# DriverPCB.net
KiCad netlist of a schematic drawn in Altium Designer
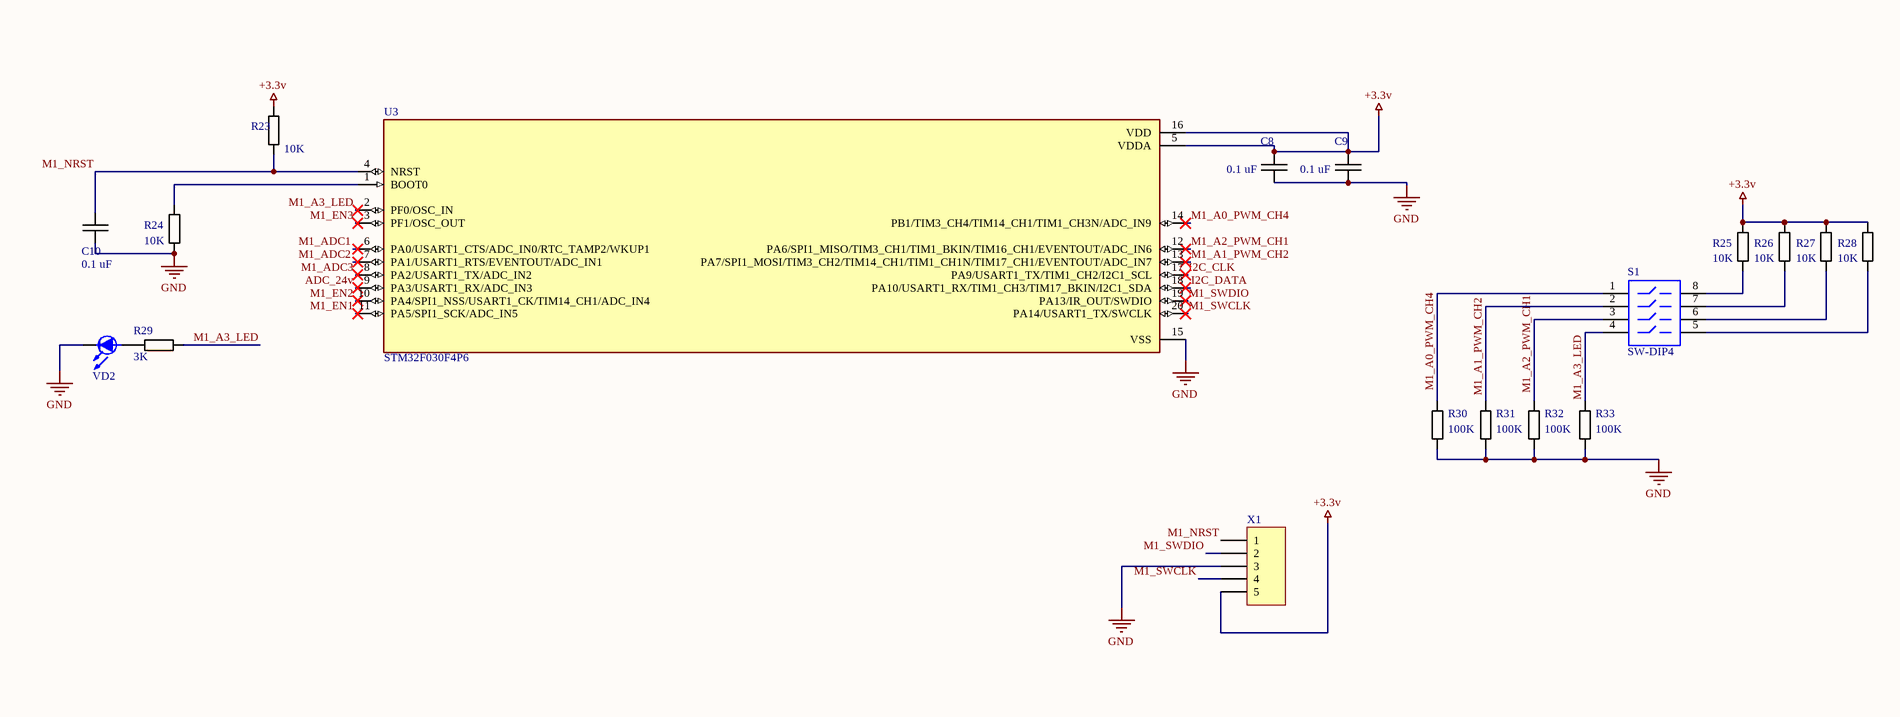
[diagram p0: DriverPCB.SchDoc, top left]
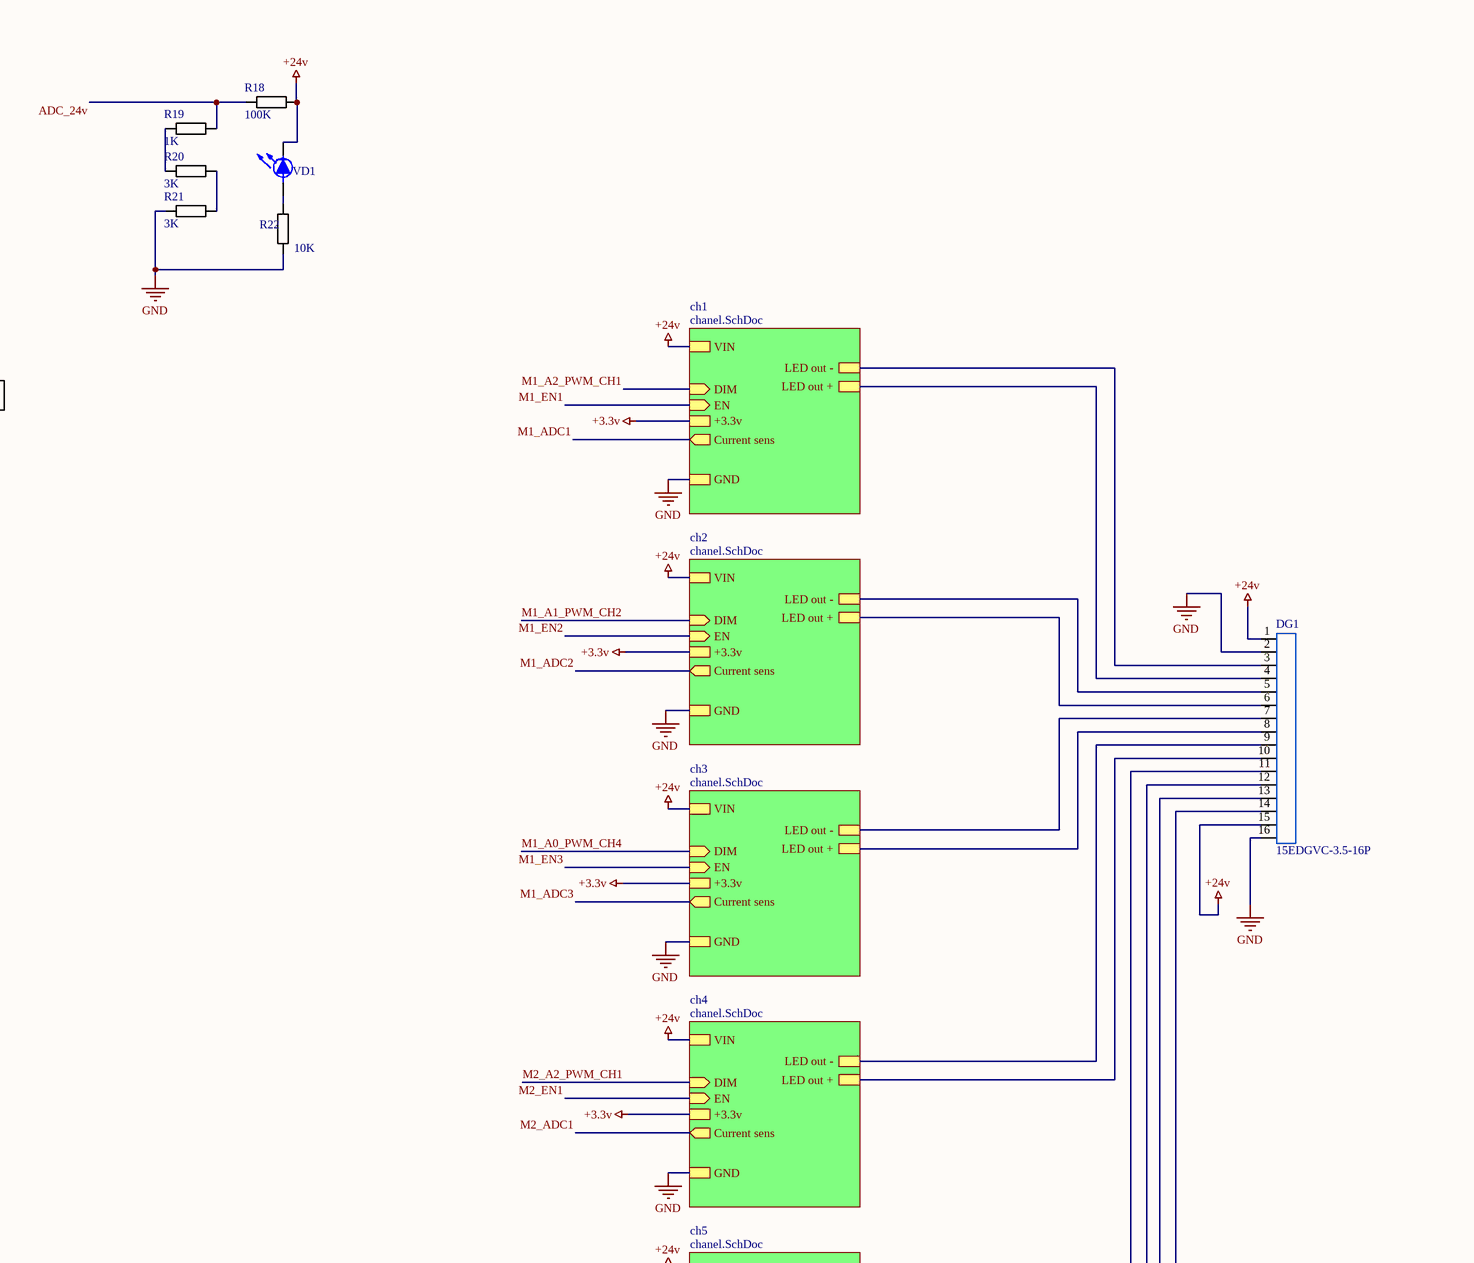
[diagram p1: DriverPCB.SchDoc, top right]
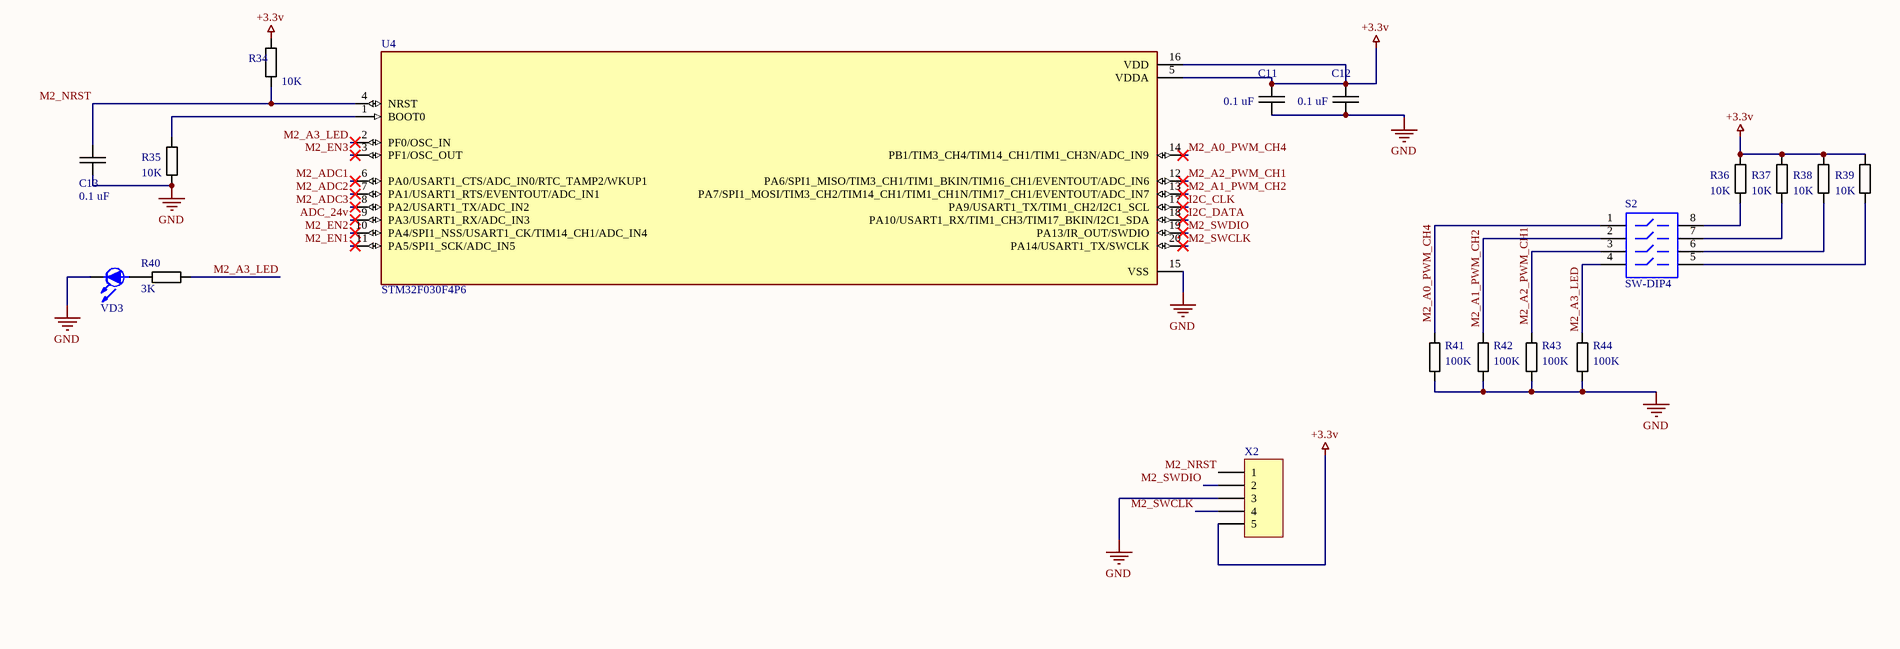
[diagram p2: DriverPCB.SchDoc, bottom left]
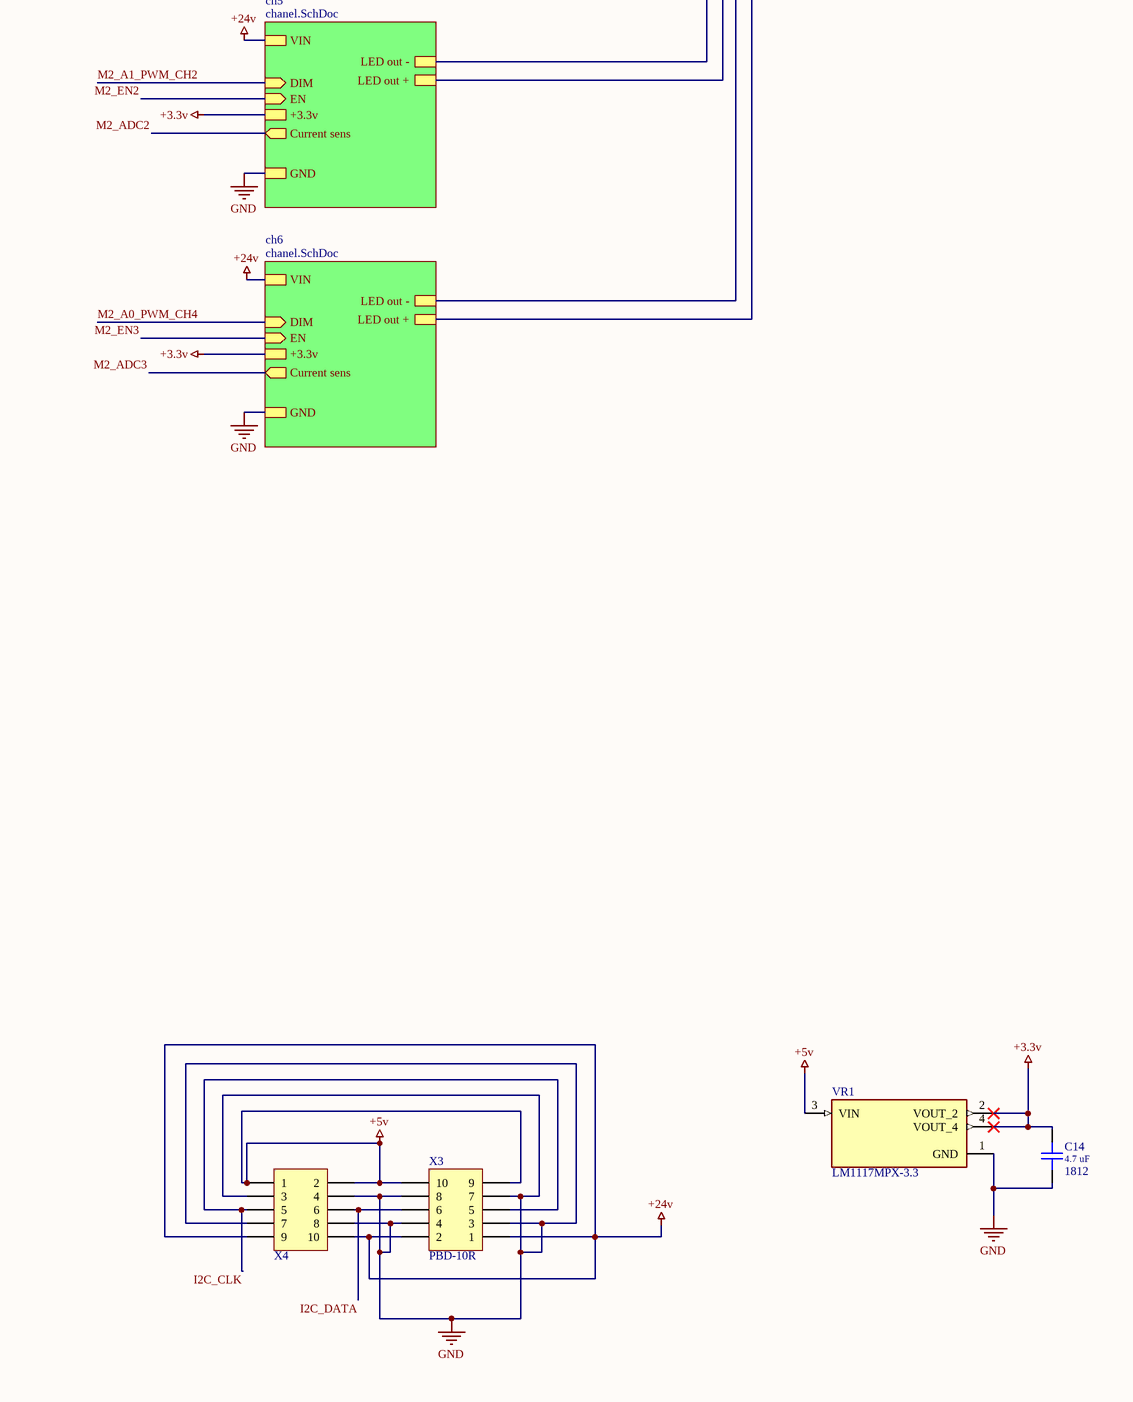
[diagram p3: DriverPCB.SchDoc, bottom right]

(export (version "E")
  (design (tool "Eeschema 10.0.6"))
  (components
    (comp (ref "C8")
      (value "0.1 uF")
      (footprint "CAPACITOR 0603")
      (libsource (lib "Maks_lib") (part "Capasitor"))
    )
    (comp (ref "C9")
      (value "0.1 uF")
      (footprint "CAPACITOR 0603")
      (libsource (lib "Maks_lib") (part "Capasitor"))
    )
    (comp (ref "C10")
      (value "0.1 uF")
      (footprint "CAPACITOR 0603")
      (libsource (lib "Maks_lib") (part "Capasitor"))
    )
    (comp (ref "C11")
      (value "0.1 uF")
      (footprint "CAPACITOR 0603")
      (libsource (lib "Maks_lib") (part "Capasitor"))
    )
    (comp (ref "C12")
      (value "0.1 uF")
      (footprint "CAPACITOR 0603")
      (libsource (lib "Maks_lib") (part "Capasitor"))
    )
    (comp (ref "C13")
      (value "0.1 uF")
      (footprint "CAPACITOR 0603")
      (libsource (lib "Maks_lib") (part "Capasitor"))
    )
    (comp (ref "C14")
      (value "4.7 uF")
      (footprint "CAPCHIP1812")
      (description "Ceramic Capacitor")
      (fields (field (name "PACKAGE") "1812") (field (name "Comment") "Cap C"))
      (libsource (lib "RCL") (part "Cap C"))
    )
    (comp (ref "DG1")
      (value "15EDGVC-3.5-16P")
      (footprint "15EDGVC-3.5-16P")
      (libsource (lib "Degson") (part "15EDGVC-3.5-16P"))
    )
    (comp (ref "R18")
      (value "100K")
      (footprint "Resistor 0402")
      (libsource (lib "Maks_lib") (part "Resistor"))
    )
    (comp (ref "R19") (value "1K") (footprint "Resistor 0402") (libsource (lib "Maks_lib") (part "Resistor")))
    (comp (ref "R20") (value "3K") (footprint "Resistor 0402") (libsource (lib "Maks_lib") (part "Resistor")))
    (comp (ref "R21") (value "3K") (footprint "Resistor 0402") (libsource (lib "Maks_lib") (part "Resistor")))
    (comp (ref "R22")
      (value "10K")
      (footprint "Resistor 0402")
      (libsource (lib "Maks_lib") (part "Resistor"))
    )
    (comp (ref "R23")
      (value "10K")
      (footprint "Resistor 0402")
      (libsource (lib "Maks_lib") (part "Resistor"))
    )
    (comp (ref "R24")
      (value "10K")
      (footprint "Resistor 0402")
      (libsource (lib "Maks_lib") (part "Resistor"))
    )
    (comp (ref "R25")
      (value "10K")
      (footprint "Resistor 0402")
      (libsource (lib "Maks_lib") (part "Resistor"))
    )
    (comp (ref "R26")
      (value "10K")
      (footprint "Resistor 0402")
      (libsource (lib "Maks_lib") (part "Resistor"))
    )
    (comp (ref "R27")
      (value "10K")
      (footprint "Resistor 0402")
      (libsource (lib "Maks_lib") (part "Resistor"))
    )
    (comp (ref "R28")
      (value "10K")
      (footprint "Resistor 0402")
      (libsource (lib "Maks_lib") (part "Resistor"))
    )
    (comp (ref "R29") (value "3K") (footprint "Resistor 0402") (libsource (lib "Maks_lib") (part "Resistor")))
    (comp (ref "R30")
      (value "100K")
      (footprint "Resistor 0402")
      (libsource (lib "Maks_lib") (part "Resistor"))
    )
    (comp (ref "R31")
      (value "100K")
      (footprint "Resistor 0402")
      (libsource (lib "Maks_lib") (part "Resistor"))
    )
    (comp (ref "R32")
      (value "100K")
      (footprint "Resistor 0402")
      (libsource (lib "Maks_lib") (part "Resistor"))
    )
    (comp (ref "R33")
      (value "100K")
      (footprint "Resistor 0402")
      (libsource (lib "Maks_lib") (part "Resistor"))
    )
    (comp (ref "R34")
      (value "10K")
      (footprint "Resistor 0402")
      (libsource (lib "Maks_lib") (part "Resistor"))
    )
    (comp (ref "R35")
      (value "10K")
      (footprint "Resistor 0402")
      (libsource (lib "Maks_lib") (part "Resistor"))
    )
    (comp (ref "R36")
      (value "10K")
      (footprint "Resistor 0402")
      (libsource (lib "Maks_lib") (part "Resistor"))
    )
    (comp (ref "R37")
      (value "10K")
      (footprint "Resistor 0402")
      (libsource (lib "Maks_lib") (part "Resistor"))
    )
    (comp (ref "R38")
      (value "10K")
      (footprint "Resistor 0402")
      (libsource (lib "Maks_lib") (part "Resistor"))
    )
    (comp (ref "R39")
      (value "10K")
      (footprint "Resistor 0402")
      (libsource (lib "Maks_lib") (part "Resistor"))
    )
    (comp (ref "R40") (value "3K") (footprint "Resistor 0402") (libsource (lib "Maks_lib") (part "Resistor")))
    (comp (ref "R41")
      (value "100K")
      (footprint "Resistor 0402")
      (libsource (lib "Maks_lib") (part "Resistor"))
    )
    (comp (ref "R42")
      (value "100K")
      (footprint "Resistor 0402")
      (libsource (lib "Maks_lib") (part "Resistor"))
    )
    (comp (ref "R43")
      (value "100K")
      (footprint "Resistor 0402")
      (libsource (lib "Maks_lib") (part "Resistor"))
    )
    (comp (ref "R44")
      (value "100K")
      (footprint "Resistor 0402")
      (libsource (lib "Maks_lib") (part "Resistor"))
    )
    (comp (ref "S1")
      (value "SW-DIP4")
      (footprint "DIP-8")
      (description "DIP Switch")
      (fields (field (name "PUBLISHER") "Altium Limited"))
      (libsource (lib "Miscellaneous Devices") (part "SW-DIP4"))
    )
    (comp (ref "S2")
      (value "SW-DIP4")
      (footprint "DIP-8")
      (description "DIP Switch")
      (fields (field (name "PUBLISHER") "Altium Limited"))
      (libsource (lib "Miscellaneous Devices") (part "SW-DIP4"))
    )
    (comp (ref "U3")
      (value "STM32F030F4P6")
      (footprint "SOP65P640X120-20N")
      (description "MCU 32-bit STM32F ARM Cortex M0 RISC 16KB Flash 2.5V/3.3V 20-Pin TSSOP Tray")
      (libsource (lib "STM32F030F4P6") (part "STM32F030F4P6"))
    )
    (comp (ref "U4")
      (value "STM32F030F4P6")
      (footprint "SOP65P640X120-20N")
      (description "MCU 32-bit STM32F ARM Cortex M0 RISC 16KB Flash 2.5V/3.3V 20-Pin TSSOP Tray")
      (libsource (lib "STM32F030F4P6") (part "STM32F030F4P6"))
    )
    (comp (ref "VD1") (value "one color") (footprint "0805-") (libsource (lib "DT") (part "LED SMD")))
    (comp (ref "VD2") (value "~") (footprint "0805-") (libsource (lib "DT") (part "LED SMD")))
    (comp (ref "VD3") (value "~") (footprint "0805-") (libsource (lib "DT") (part "LED SMD")))
    (comp (ref "VR1")
      (value "LM1117MPX-3.3")
      (footprint "VREG_LM1117MPX-3.3")
      (description "800-mA 15-V linear voltage regulator")
      (fields (field (name "MF") "Texas Instruments"))
      (libsource (lib "LM1117MPX-3.3") (part "LM1117MPX-3.3"))
    )
    (comp (ref "X1")
      (value "~")
      (footprint "PLS-5-3D")
      (description "Header, 5-Pin")
      (fields (field (name "PARTNUMBER") "PLS-5"))
      (libsource (lib "AX_Altium_v2.3") (part "PLS-5"))
    )
    (comp (ref "X2")
      (value "~")
      (footprint "PLS-5-3D")
      (description "Header, 5-Pin")
      (fields (field (name "PARTNUMBER") "PLS-5"))
      (libsource (lib "AX_Altium_v2.3") (part "PLS-5"))
    )
    (comp (ref "X3")
      (value "PBD-10R")
      (footprint "PBD-10RR")
      (description "Header, 5-Pin, Dual row")
      (libsource (lib "AX_Altium_v2.3") (part "PBD-10R"))
    )
    (comp (ref "X4")
      (value "PLD-10R")
      (footprint "PLD-10RR1")
      (description "Header, 5-Pin, Dual row")
      (libsource (lib "AX_Altium_v2.3") (part "PLD-10R"))
    )
  )
  (nets
    (net (code "1") (name "+3.3v") (class "Default")
      (node (ref "C11") (pin "1") (pinfunction "1_1") (pintype "passive"))
      (node (ref "C12") (pin "1") (pinfunction "1_1") (pintype "passive"))
      (node (ref "C14") (pin "2") (pinfunction "2_2") (pintype "passive"))
      (node (ref "C8") (pin "1") (pinfunction "1_1") (pintype "passive"))
      (node (ref "C9") (pin "1") (pinfunction "1_1") (pintype "passive"))
      (node (ref "R23") (pin "2") (pinfunction "2_2") (pintype "passive"))
      (node (ref "R25") (pin "1") (pinfunction "1_1") (pintype "passive"))
      (node (ref "R26") (pin "1") (pinfunction "1_1") (pintype "passive"))
      (node (ref "R27") (pin "1") (pinfunction "1_1") (pintype "passive"))
      (node (ref "R28") (pin "1") (pinfunction "1_1") (pintype "passive"))
      (node (ref "R34") (pin "2") (pinfunction "2_2") (pintype "passive"))
      (node (ref "R36") (pin "1") (pinfunction "1_1") (pintype "passive"))
      (node (ref "R37") (pin "1") (pinfunction "1_1") (pintype "passive"))
      (node (ref "R38") (pin "1") (pinfunction "1_1") (pintype "passive"))
      (node (ref "R39") (pin "1") (pinfunction "1_1") (pintype "passive"))
      (node (ref "U3") (pin "16") (pinfunction "VDD_16") (pintype "power_in"))
      (node (ref "U3") (pin "5") (pinfunction "VDDA_5") (pintype "power_in"))
      (node (ref "U4") (pin "16") (pinfunction "VDD_16") (pintype "power_in"))
      (node (ref "U4") (pin "5") (pinfunction "VDDA_5") (pintype "power_in"))
      (node (ref "VR1") (pin "2") (pinfunction "VOUT_2_2") (pintype "output"))
      (node (ref "VR1") (pin "4") (pinfunction "VOUT_4_4") (pintype "output"))
      (node (ref "X1") (pin "5") (pinfunction "5_5") (pintype "passive"))
      (node (ref "X2") (pin "5") (pinfunction "5_5") (pintype "passive"))
    )
    (net (code "2") (name "+5v") (class "Default")
      (node (ref "VR1") (pin "3") (pinfunction "VIN_3") (pintype "input"))
      (node (ref "X3") (pin "10") (pinfunction "10_10") (pintype "passive"))
      (node (ref "X3") (pin "9") (pinfunction "9_9") (pintype "passive"))
      (node (ref "X4") (pin "1") (pinfunction "1_1") (pintype "passive"))
      (node (ref "X4") (pin "2") (pinfunction "2_2") (pintype "passive"))
    )
    (net (code "3") (name "+24v") (class "Default")
      (node (ref "DG1") (pin "1") (pintype "passive"))
      (node (ref "DG1") (pin "15") (pintype "passive"))
      (node (ref "R18") (pin "1") (pinfunction "1_1") (pintype "passive"))
      (node (ref "VD1") (pin "K") (pinfunction "k_K") (pintype "passive"))
      (node (ref "X3") (pin "1") (pinfunction "1_1") (pintype "passive"))
      (node (ref "X3") (pin "2") (pinfunction "2_2") (pintype "passive"))
      (node (ref "X4") (pin "10") (pinfunction "10_10") (pintype "passive"))
      (node (ref "X4") (pin "9") (pinfunction "9_9") (pintype "passive"))
    )
    (net (code "4") (name "/ADC_24v") (class "Default")
      (node (ref "R18") (pin "2") (pinfunction "2_2") (pintype "passive"))
      (node (ref "R19") (pin "2") (pinfunction "2_2") (pintype "passive"))
      (node (ref "U3") (pin "9") (pinfunction "PA3/USART1_RX/ADC_IN3_9") (pintype "bidirectional"))
      (node (ref "U4") (pin "9") (pinfunction "PA3/USART1_RX/ADC_IN3_9") (pintype "bidirectional"))
    )
    (net (code "7") (name "/I2C_CLK") (class "Default")
      (node (ref "U3") (pin "17") (pinfunction "PA9/USART1_TX/TIM1_CH2/I2C1_SCL_17") (pintype "bidirectional"))
      (node (ref "U4") (pin "17") (pinfunction "PA9/USART1_TX/TIM1_CH2/I2C1_SCL_17") (pintype "bidirectional"))
      (node (ref "X3") (pin "5") (pinfunction "5_5") (pintype "passive"))
      (node (ref "X4") (pin "5") (pinfunction "5_5") (pintype "passive"))
    )
    (net (code "8") (name "/I2C_DATA") (class "Default")
      (node (ref "U3") (pin "18") (pinfunction "PA10/USART1_RX/TIM1_CH3/TIM17_BKIN/I2C1_SDA_18") (pintype "bidirectional"))
      (node (ref "U4") (pin "18") (pinfunction "PA10/USART1_RX/TIM1_CH3/TIM17_BKIN/I2C1_SDA_18") (pintype "bidirectional"))
      (node (ref "X3") (pin "6") (pinfunction "6_6") (pintype "passive"))
      (node (ref "X4") (pin "6") (pinfunction "6_6") (pintype "passive"))
    )
    (net (code "9") (name "/LED out +") (class "Default") (node (ref "DG1") (pin "12") (pintype "passive")))
    (net (code "10") (name "/LED out +_1") (class "Default")
      (node (ref "DG1") (pin "14") (pintype "passive"))
    )
    (net (code "11") (name "/LED out +_2") (class "Default") (node (ref "DG1") (pin "8") (pintype "passive")))
    (net (code "12") (name "/LED out +_3") (class "Default") (node (ref "DG1") (pin "6") (pintype "passive")))
    (net (code "13") (name "/LED out +_4") (class "Default") (node (ref "DG1") (pin "4") (pintype "passive")))
    (net (code "14") (name "/LED out +_5") (class "Default")
      (node (ref "DG1") (pin "10") (pintype "passive"))
    )
    (net (code "15") (name "/LED out -") (class "Default") (node (ref "DG1") (pin "9") (pintype "passive")))
    (net (code "16") (name "/LED out -_1") (class "Default")
      (node (ref "DG1") (pin "13") (pintype "passive"))
    )
    (net (code "17") (name "/LED out -_2") (class "Default") (node (ref "DG1") (pin "5") (pintype "passive")))
    (net (code "18") (name "/LED out -_3") (class "Default") (node (ref "DG1") (pin "7") (pintype "passive")))
    (net (code "19") (name "/LED out -_4") (class "Default") (node (ref "DG1") (pin "3") (pintype "passive")))
    (net (code "20") (name "/LED out -_5") (class "Default")
      (node (ref "DG1") (pin "11") (pintype "passive"))
    )
    (net (code "21") (name "/M1_A0_PWM_CH4") (class "Default")
      (node (ref "R30") (pin "1") (pinfunction "1_1") (pintype "passive"))
      (node (ref "S1") (pin "1") (pinfunction "1_1") (pintype "passive"))
      (node (ref "U3") (pin "14") (pinfunction "PB1/TIM3_CH4/TIM14_CH1/TIM1_CH3N/ADC_IN9_14") (pintype "bidirectional"))
    )
    (net (code "22") (name "/M1_A1_PWM_CH2") (class "Default")
      (node (ref "R31") (pin "1") (pinfunction "1_1") (pintype "passive"))
      (node (ref "S1") (pin "2") (pinfunction "2_2") (pintype "passive"))
      (node (ref "U3") (pin "13") (pinfunction "PA7/SPI1_MOSI/TIM3_CH2/TIM14_CH1/TIM1_CH1N/TIM17_CH1/EVENTOUT/ADC_IN7_13") (pintype "bidirectional"))
    )
    (net (code "23") (name "/M1_A2_PWM_CH1") (class "Default")
      (node (ref "R32") (pin "1") (pinfunction "1_1") (pintype "passive"))
      (node (ref "S1") (pin "3") (pinfunction "3_3") (pintype "passive"))
      (node (ref "U3") (pin "12") (pinfunction "PA6/SPI1_MISO/TIM3_CH1/TIM1_BKIN/TIM16_CH1/EVENTOUT/ADC_IN6_12") (pintype "bidirectional"))
    )
    (net (code "24") (name "/M1_A3_LED") (class "Default")
      (node (ref "R29") (pin "1") (pinfunction "1_1") (pintype "passive"))
      (node (ref "R33") (pin "1") (pinfunction "1_1") (pintype "passive"))
      (node (ref "S1") (pin "4") (pinfunction "4_4") (pintype "passive"))
      (node (ref "U3") (pin "2") (pinfunction "PF0/OSC_IN_2") (pintype "bidirectional"))
    )
    (net (code "25") (name "/M1_ADC1") (class "Default")
      (node (ref "U3") (pin "6") (pinfunction "PA0/USART1_CTS/ADC_IN0/RTC_TAMP2/WKUP1_6") (pintype "bidirectional+no_connect"))
    )
    (net (code "26") (name "/M1_ADC2") (class "Default")
      (node (ref "U3") (pin "7") (pinfunction "PA1/USART1_RTS/EVENTOUT/ADC_IN1_7") (pintype "bidirectional+no_connect"))
    )
    (net (code "27") (name "/M1_ADC3") (class "Default")
      (node (ref "U3") (pin "8") (pinfunction "PA2/USART1_TX/ADC_IN2_8") (pintype "bidirectional+no_connect"))
    )
    (net (code "28") (name "/M1_EN1") (class "Default")
      (node (ref "U3") (pin "11") (pinfunction "PA5/SPI1_SCK/ADC_IN5_11") (pintype "bidirectional+no_connect"))
    )
    (net (code "29") (name "/M1_EN2") (class "Default")
      (node (ref "U3") (pin "10") (pinfunction "PA4/SPI1_NSS/USART1_CK/TIM14_CH1/ADC_IN4_10") (pintype "bidirectional+no_connect"))
    )
    (net (code "30") (name "/M1_EN3") (class "Default")
      (node (ref "U3") (pin "3") (pinfunction "PF1/OSC_OUT_3") (pintype "bidirectional+no_connect"))
    )
    (net (code "31") (name "/M1_NRST") (class "Default")
      (node (ref "C10") (pin "2") (pinfunction "2_2") (pintype "passive"))
      (node (ref "R23") (pin "1") (pinfunction "1_1") (pintype "passive"))
      (node (ref "U3") (pin "4") (pinfunction "NRST_4") (pintype "bidirectional"))
      (node (ref "X1") (pin "1") (pinfunction "1_1") (pintype "passive"))
    )
    (net (code "32") (name "/M1_SWCLK") (class "Default")
      (node (ref "U3") (pin "20") (pinfunction "PA14/USART1_TX/SWCLK_20") (pintype "bidirectional"))
      (node (ref "X1") (pin "4") (pinfunction "4_4") (pintype "passive"))
    )
    (net (code "33") (name "/M1_SWDIO") (class "Default")
      (node (ref "U3") (pin "19") (pinfunction "PA13/IR_OUT/SWDIO_19") (pintype "bidirectional"))
      (node (ref "X1") (pin "2") (pinfunction "2_2") (pintype "passive"))
    )
    (net (code "34") (name "/M2_A0_PWM_CH4") (class "Default")
      (node (ref "R41") (pin "1") (pinfunction "1_1") (pintype "passive"))
      (node (ref "S2") (pin "1") (pinfunction "1_1") (pintype "passive"))
      (node (ref "U4") (pin "14") (pinfunction "PB1/TIM3_CH4/TIM14_CH1/TIM1_CH3N/ADC_IN9_14") (pintype "bidirectional"))
    )
    (net (code "35") (name "/M2_A1_PWM_CH2") (class "Default")
      (node (ref "R42") (pin "1") (pinfunction "1_1") (pintype "passive"))
      (node (ref "S2") (pin "2") (pinfunction "2_2") (pintype "passive"))
      (node (ref "U4") (pin "13") (pinfunction "PA7/SPI1_MOSI/TIM3_CH2/TIM14_CH1/TIM1_CH1N/TIM17_CH1/EVENTOUT/ADC_IN7_13") (pintype "bidirectional"))
    )
    (net (code "36") (name "/M2_A2_PWM_CH1") (class "Default")
      (node (ref "R43") (pin "1") (pinfunction "1_1") (pintype "passive"))
      (node (ref "S2") (pin "3") (pinfunction "3_3") (pintype "passive"))
      (node (ref "U4") (pin "12") (pinfunction "PA6/SPI1_MISO/TIM3_CH1/TIM1_BKIN/TIM16_CH1/EVENTOUT/ADC_IN6_12") (pintype "bidirectional"))
    )
    (net (code "37") (name "/M2_A3_LED") (class "Default")
      (node (ref "R40") (pin "1") (pinfunction "1_1") (pintype "passive"))
      (node (ref "R44") (pin "1") (pinfunction "1_1") (pintype "passive"))
      (node (ref "S2") (pin "4") (pinfunction "4_4") (pintype "passive"))
      (node (ref "U4") (pin "2") (pinfunction "PF0/OSC_IN_2") (pintype "bidirectional"))
    )
    (net (code "38") (name "/M2_ADC1") (class "Default")
      (node (ref "U4") (pin "6") (pinfunction "PA0/USART1_CTS/ADC_IN0/RTC_TAMP2/WKUP1_6") (pintype "bidirectional+no_connect"))
    )
    (net (code "39") (name "/M2_ADC2") (class "Default")
      (node (ref "U4") (pin "7") (pinfunction "PA1/USART1_RTS/EVENTOUT/ADC_IN1_7") (pintype "bidirectional+no_connect"))
    )
    (net (code "40") (name "/M2_ADC3") (class "Default")
      (node (ref "U4") (pin "8") (pinfunction "PA2/USART1_TX/ADC_IN2_8") (pintype "bidirectional+no_connect"))
    )
    (net (code "41") (name "/M2_EN1") (class "Default")
      (node (ref "U4") (pin "11") (pinfunction "PA5/SPI1_SCK/ADC_IN5_11") (pintype "bidirectional+no_connect"))
    )
    (net (code "42") (name "/M2_EN2") (class "Default")
      (node (ref "U4") (pin "10") (pinfunction "PA4/SPI1_NSS/USART1_CK/TIM14_CH1/ADC_IN4_10") (pintype "bidirectional+no_connect"))
    )
    (net (code "43") (name "/M2_EN3") (class "Default")
      (node (ref "U4") (pin "3") (pinfunction "PF1/OSC_OUT_3") (pintype "bidirectional+no_connect"))
    )
    (net (code "44") (name "/M2_NRST") (class "Default")
      (node (ref "C13") (pin "2") (pinfunction "2_2") (pintype "passive"))
      (node (ref "R34") (pin "1") (pinfunction "1_1") (pintype "passive"))
      (node (ref "U4") (pin "4") (pinfunction "NRST_4") (pintype "bidirectional"))
      (node (ref "X2") (pin "1") (pinfunction "1_1") (pintype "passive"))
    )
    (net (code "45") (name "/M2_SWCLK") (class "Default")
      (node (ref "U4") (pin "20") (pinfunction "PA14/USART1_TX/SWCLK_20") (pintype "bidirectional"))
      (node (ref "X2") (pin "4") (pinfunction "4_4") (pintype "passive"))
    )
    (net (code "46") (name "/M2_SWDIO") (class "Default")
      (node (ref "U4") (pin "19") (pinfunction "PA13/IR_OUT/SWDIO_19") (pintype "bidirectional"))
      (node (ref "X2") (pin "2") (pinfunction "2_2") (pintype "passive"))
    )
    (net (code "47") (name "GND") (class "Default")
      (node (ref "C10") (pin "1") (pinfunction "1_1") (pintype "passive"))
      (node (ref "C11") (pin "2") (pinfunction "2_2") (pintype "passive"))
      (node (ref "C12") (pin "2") (pinfunction "2_2") (pintype "passive"))
      (node (ref "C13") (pin "1") (pinfunction "1_1") (pintype "passive"))
      (node (ref "C14") (pin "1") (pinfunction "1_1") (pintype "passive"))
      (node (ref "C8") (pin "2") (pinfunction "2_2") (pintype "passive"))
      (node (ref "C9") (pin "2") (pinfunction "2_2") (pintype "passive"))
      (node (ref "DG1") (pin "16") (pintype "passive"))
      (node (ref "DG1") (pin "2") (pintype "passive"))
      (node (ref "R21") (pin "1") (pinfunction "1_1") (pintype "passive"))
      (node (ref "R22") (pin "1") (pinfunction "1_1") (pintype "passive"))
      (node (ref "R24") (pin "2") (pinfunction "2_2") (pintype "passive"))
      (node (ref "R30") (pin "2") (pinfunction "2_2") (pintype "passive"))
      (node (ref "R31") (pin "2") (pinfunction "2_2") (pintype "passive"))
      (node (ref "R32") (pin "2") (pinfunction "2_2") (pintype "passive"))
      (node (ref "R33") (pin "2") (pinfunction "2_2") (pintype "passive"))
      (node (ref "R35") (pin "2") (pinfunction "2_2") (pintype "passive"))
      (node (ref "R41") (pin "2") (pinfunction "2_2") (pintype "passive"))
      (node (ref "R42") (pin "2") (pinfunction "2_2") (pintype "passive"))
      (node (ref "R43") (pin "2") (pinfunction "2_2") (pintype "passive"))
      (node (ref "R44") (pin "2") (pinfunction "2_2") (pintype "passive"))
      (node (ref "U3") (pin "15") (pinfunction "VSS_15") (pintype "power_in"))
      (node (ref "U4") (pin "15") (pinfunction "VSS_15") (pintype "power_in"))
      (node (ref "VD2") (pin "K") (pinfunction "k_K") (pintype "passive"))
      (node (ref "VD3") (pin "K") (pinfunction "k_K") (pintype "passive"))
      (node (ref "VR1") (pin "1") (pinfunction "GND_1") (pintype "power_in"))
      (node (ref "X1") (pin "3") (pinfunction "3_3") (pintype "passive"))
      (node (ref "X2") (pin "3") (pinfunction "3_3") (pintype "passive"))
      (node (ref "X3") (pin "3") (pinfunction "3_3") (pintype "passive"))
      (node (ref "X3") (pin "4") (pinfunction "4_4") (pintype "passive"))
      (node (ref "X3") (pin "7") (pinfunction "7_7") (pintype "passive"))
      (node (ref "X3") (pin "8") (pinfunction "8_8") (pintype "passive"))
      (node (ref "X4") (pin "3") (pinfunction "3_3") (pintype "passive"))
      (node (ref "X4") (pin "4") (pinfunction "4_4") (pintype "passive"))
      (node (ref "X4") (pin "7") (pinfunction "7_7") (pintype "passive"))
      (node (ref "X4") (pin "8") (pinfunction "8_8") (pintype "passive"))
    )
    (net (code "48") (name "Net-(R19-Pad1)") (class "Default")
      (node (ref "R19") (pin "1") (pinfunction "1_1") (pintype "passive"))
      (node (ref "R20") (pin "1") (pinfunction "1_1") (pintype "passive"))
    )
    (net (code "49") (name "Net-(R20-Pad2)") (class "Default")
      (node (ref "R20") (pin "2") (pinfunction "2_2") (pintype "passive"))
      (node (ref "R21") (pin "2") (pinfunction "2_2") (pintype "passive"))
    )
    (net (code "50") (name "Net-(R25-Pad2)") (class "Default")
      (node (ref "R25") (pin "2") (pinfunction "2_2") (pintype "passive"))
      (node (ref "S1") (pin "8") (pinfunction "8_8") (pintype "passive"))
    )
    (net (code "51") (name "Net-(R26-Pad2)") (class "Default")
      (node (ref "R26") (pin "2") (pinfunction "2_2") (pintype "passive"))
      (node (ref "S1") (pin "7") (pinfunction "7_7") (pintype "passive"))
    )
    (net (code "52") (name "Net-(R27-Pad2)") (class "Default")
      (node (ref "R27") (pin "2") (pinfunction "2_2") (pintype "passive"))
      (node (ref "S1") (pin "6") (pinfunction "6_6") (pintype "passive"))
    )
    (net (code "53") (name "Net-(R28-Pad2)") (class "Default")
      (node (ref "R28") (pin "2") (pinfunction "2_2") (pintype "passive"))
      (node (ref "S1") (pin "5") (pinfunction "5_5") (pintype "passive"))
    )
    (net (code "54") (name "Net-(R36-Pad2)") (class "Default")
      (node (ref "R36") (pin "2") (pinfunction "2_2") (pintype "passive"))
      (node (ref "S2") (pin "8") (pinfunction "8_8") (pintype "passive"))
    )
    (net (code "55") (name "Net-(R37-Pad2)") (class "Default")
      (node (ref "R37") (pin "2") (pinfunction "2_2") (pintype "passive"))
      (node (ref "S2") (pin "7") (pinfunction "7_7") (pintype "passive"))
    )
    (net (code "56") (name "Net-(R38-Pad2)") (class "Default")
      (node (ref "R38") (pin "2") (pinfunction "2_2") (pintype "passive"))
      (node (ref "S2") (pin "6") (pinfunction "6_6") (pintype "passive"))
    )
    (net (code "57") (name "Net-(R39-Pad2)") (class "Default")
      (node (ref "R39") (pin "2") (pinfunction "2_2") (pintype "passive"))
      (node (ref "S2") (pin "5") (pinfunction "5_5") (pintype "passive"))
    )
    (net (code "58") (name "Net-(U3-BOOT0)") (class "Default")
      (node (ref "R24") (pin "1") (pinfunction "1_1") (pintype "passive"))
      (node (ref "U3") (pin "1") (pinfunction "BOOT0_1") (pintype "input"))
    )
    (net (code "59") (name "Net-(U4-BOOT0)") (class "Default")
      (node (ref "R35") (pin "1") (pinfunction "1_1") (pintype "passive"))
      (node (ref "U4") (pin "1") (pinfunction "BOOT0_1") (pintype "input"))
    )
    (net (code "60") (name "Net-(VD1-a)") (class "Default")
      (node (ref "R22") (pin "2") (pinfunction "2_2") (pintype "passive"))
      (node (ref "VD1") (pin "A") (pinfunction "a_A") (pintype "passive"))
    )
    (net (code "61") (name "Net-(VD2-a)") (class "Default")
      (node (ref "R29") (pin "2") (pinfunction "2_2") (pintype "passive"))
      (node (ref "VD2") (pin "A") (pinfunction "a_A") (pintype "passive"))
    )
    (net (code "62") (name "Net-(VD3-a)") (class "Default")
      (node (ref "R40") (pin "2") (pinfunction "2_2") (pintype "passive"))
      (node (ref "VD3") (pin "A") (pinfunction "a_A") (pintype "passive"))
    )
  )
)
